# sensorHub.net
KiCad netlist of a schematic drawn in EAGLE
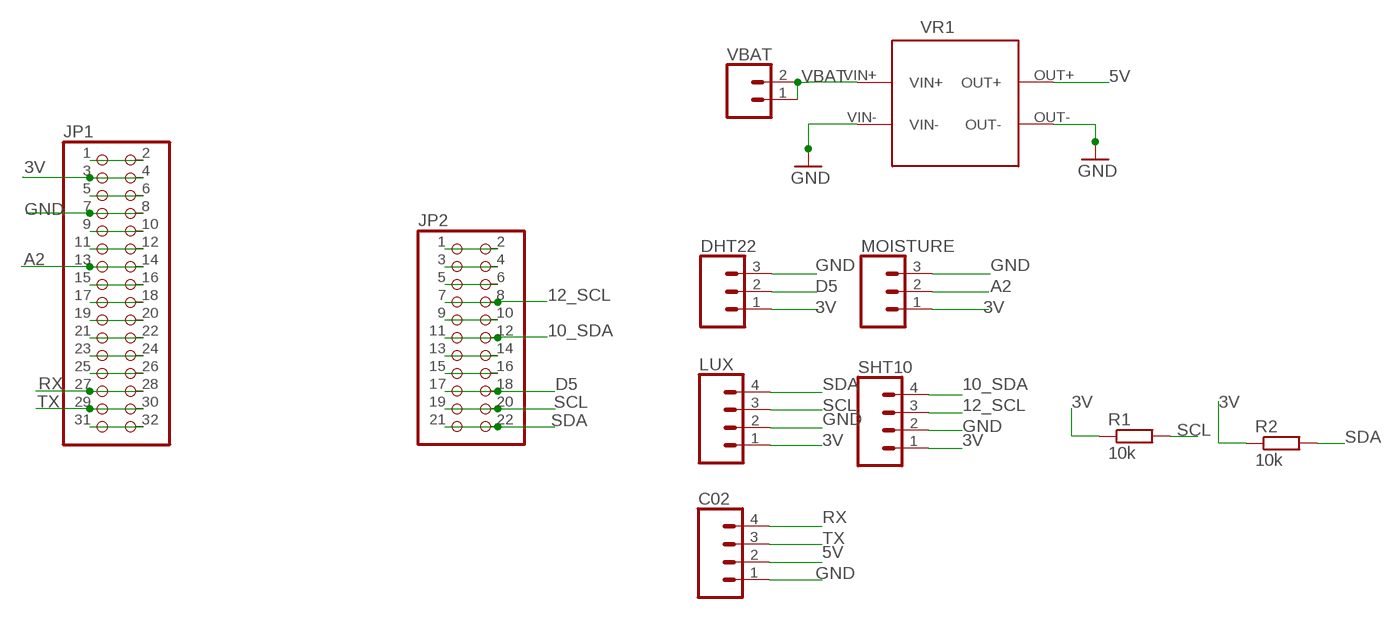
[diagram p0: schematic, sheet 1]

(export (version "E")
  (design (tool "Eeschema 10.0.6"))
  (components
    (comp (ref "C02")
      (value "CONN_04SCREW")
      (footprint "eagle-import:SCREWTERMINAL-3.5MM-4")
      (libsource (lib "eagle-import") (part "CONN_04SCREW"))
    )
    (comp (ref "DHT22")
      (value "CONN_03SCREW")
      (footprint "eagle-import:SCREWTERMINAL-3.5MM-3")
      (libsource (lib "eagle-import") (part "CONN_03SCREW"))
    )
    (comp (ref "JP1")
      (value "PINHD-2X16")
      (footprint "eagle-import:2X16")
      (libsource (lib "eagle-import") (part "PINHD-2X16"))
    )
    (comp (ref "JP2")
      (value "PINHD-2X11")
      (footprint "eagle-import:2X11")
      (libsource (lib "eagle-import") (part "PINHD-2X11"))
    )
    (comp (ref "LUX")
      (value "CONN_04SCREW")
      (footprint "eagle-import:SCREWTERMINAL-3.5MM-4")
      (libsource (lib "eagle-import") (part "CONN_04SCREW"))
    )
    (comp (ref "MOISTURE")
      (value "CONN_03SCREW")
      (footprint "eagle-import:SCREWTERMINAL-3.5MM-3")
      (libsource (lib "eagle-import") (part "CONN_03SCREW"))
    )
    (comp (ref "R1")
      (value "10k")
      (footprint "eagle-import:0207_10")
      (libsource (lib "eagle-import") (part "R-EU_0207/10"))
    )
    (comp (ref "R2")
      (value "10k")
      (footprint "eagle-import:0207_10")
      (libsource (lib "eagle-import") (part "R-EU_0207/10"))
    )
    (comp (ref "SHT10")
      (value "CONN_04SCREW")
      (footprint "eagle-import:SCREWTERMINAL-3.5MM-4")
      (libsource (lib "eagle-import") (part "CONN_04SCREW"))
    )
    (comp (ref "VBAT")
      (value "CONN_02")
      (footprint "eagle-import:1X02")
      (libsource (lib "eagle-import") (part "CONN_02"))
    )
    (comp (ref "VR1")
      (value "MT3608THROUGH_HOLE")
      (footprint "eagle-import:MT3608")
      (libsource (lib "eagle-import") (part "MT3608THROUGH_HOLE"))
    )
  )
  (nets
    (net (code "1") (name "/3V") (class "Default")
      (node (ref "DHT22") (pin "1") (pinfunction "1_1") (pintype "passive"))
      (node (ref "JP1") (pin "3") (pinfunction "3_3") (pintype "passive"))
      (node (ref "JP1") (pin "4") (pinfunction "4_4") (pintype "passive"))
      (node (ref "LUX") (pin "1") (pinfunction "1_1") (pintype "passive"))
      (node (ref "MOISTURE") (pin "1") (pinfunction "1_1") (pintype "passive"))
      (node (ref "R1") (pin "1") (pinfunction "1_1") (pintype "passive"))
      (node (ref "R2") (pin "1") (pinfunction "1_1") (pintype "passive"))
      (node (ref "SHT10") (pin "1") (pinfunction "1_1") (pintype "passive"))
    )
    (net (code "2") (name "/5V") (class "Default")
      (node (ref "C02") (pin "2") (pinfunction "2_2") (pintype "passive"))
      (node (ref "VR1") (pin "OUT+") (pinfunction "OUT+_OUT+") (pintype "power_in"))
    )
    (net (code "3") (name "/10_SDA") (class "Default")
      (node (ref "JP2") (pin "11") (pinfunction "11_11") (pintype "passive"))
      (node (ref "JP2") (pin "12") (pinfunction "12_12") (pintype "passive"))
      (node (ref "SHT10") (pin "4") (pinfunction "4_4") (pintype "passive"))
    )
    (net (code "4") (name "/12_SCL") (class "Default")
      (node (ref "JP2") (pin "7") (pinfunction "7_7") (pintype "passive"))
      (node (ref "JP2") (pin "8") (pinfunction "8_8") (pintype "passive"))
      (node (ref "SHT10") (pin "3") (pinfunction "3_3") (pintype "passive"))
    )
    (net (code "5") (name "/A2") (class "Default")
      (node (ref "JP1") (pin "13") (pinfunction "13_13") (pintype "passive"))
      (node (ref "JP1") (pin "14") (pinfunction "14_14") (pintype "passive"))
      (node (ref "MOISTURE") (pin "2") (pinfunction "2_2") (pintype "passive"))
    )
    (net (code "6") (name "/D5") (class "Default")
      (node (ref "DHT22") (pin "2") (pinfunction "2_2") (pintype "passive"))
      (node (ref "JP2") (pin "17") (pinfunction "17_17") (pintype "passive"))
      (node (ref "JP2") (pin "18") (pinfunction "18_18") (pintype "passive"))
    )
    (net (code "7") (name "/RX") (class "Default")
      (node (ref "C02") (pin "4") (pinfunction "4_4") (pintype "passive"))
      (node (ref "JP1") (pin "27") (pinfunction "27_27") (pintype "passive"))
      (node (ref "JP1") (pin "28") (pinfunction "28_28") (pintype "passive"))
    )
    (net (code "8") (name "/SCL") (class "Default")
      (node (ref "JP2") (pin "19") (pinfunction "19_19") (pintype "passive"))
      (node (ref "JP2") (pin "20") (pinfunction "20_20") (pintype "passive"))
      (node (ref "LUX") (pin "3") (pinfunction "3_3") (pintype "passive"))
      (node (ref "R1") (pin "2") (pinfunction "2_2") (pintype "passive"))
    )
    (net (code "9") (name "/SDA") (class "Default")
      (node (ref "JP2") (pin "21") (pinfunction "21_21") (pintype "passive"))
      (node (ref "JP2") (pin "22") (pinfunction "22_22") (pintype "passive"))
      (node (ref "LUX") (pin "4") (pinfunction "4_4") (pintype "passive"))
      (node (ref "R2") (pin "2") (pinfunction "2_2") (pintype "passive"))
    )
    (net (code "10") (name "/TX") (class "Default")
      (node (ref "C02") (pin "3") (pinfunction "3_3") (pintype "passive"))
      (node (ref "JP1") (pin "29") (pinfunction "29_29") (pintype "passive"))
      (node (ref "JP1") (pin "30") (pinfunction "30_30") (pintype "passive"))
    )
    (net (code "11") (name "/VBAT") (class "Default")
      (node (ref "VBAT") (pin "1") (pinfunction "1_1") (pintype "passive"))
      (node (ref "VBAT") (pin "2") (pinfunction "2_2") (pintype "passive"))
      (node (ref "VR1") (pin "VIN+") (pinfunction "VIN+_VIN+") (pintype "power_in"))
    )
    (net (code "12") (name "GND") (class "Default")
      (node (ref "C02") (pin "1") (pinfunction "1_1") (pintype "passive"))
      (node (ref "DHT22") (pin "3") (pinfunction "3_3") (pintype "passive"))
      (node (ref "JP1") (pin "7") (pinfunction "7_7") (pintype "passive"))
      (node (ref "JP1") (pin "8") (pinfunction "8_8") (pintype "passive"))
      (node (ref "LUX") (pin "2") (pinfunction "2_2") (pintype "passive"))
      (node (ref "MOISTURE") (pin "3") (pinfunction "3_3") (pintype "passive"))
      (node (ref "SHT10") (pin "2") (pinfunction "2_2") (pintype "passive"))
      (node (ref "VR1") (pin "OUT-") (pinfunction "OUT-_OUT-") (pintype "power_in"))
      (node (ref "VR1") (pin "VIN-") (pinfunction "VIN-_VIN-") (pintype "power_in"))
    )
    (net (code "13") (name "Net-(JP1-Pad1)") (class "Default")
      (node (ref "JP1") (pin "1") (pinfunction "1_1") (pintype "passive"))
      (node (ref "JP1") (pin "2") (pinfunction "2_2") (pintype "passive"))
    )
    (net (code "14") (name "Net-(JP1-Pad5)") (class "Default")
      (node (ref "JP1") (pin "5") (pinfunction "5_5") (pintype "passive"))
      (node (ref "JP1") (pin "6") (pinfunction "6_6") (pintype "passive"))
    )
    (net (code "15") (name "Net-(JP1-Pad10)") (class "Default")
      (node (ref "JP1") (pin "10") (pinfunction "10_10") (pintype "passive"))
      (node (ref "JP1") (pin "9") (pinfunction "9_9") (pintype "passive"))
    )
    (net (code "16") (name "Net-(JP1-Pad11)") (class "Default")
      (node (ref "JP1") (pin "11") (pinfunction "11_11") (pintype "passive"))
      (node (ref "JP1") (pin "12") (pinfunction "12_12") (pintype "passive"))
    )
    (net (code "17") (name "Net-(JP1-Pad15)") (class "Default")
      (node (ref "JP1") (pin "15") (pinfunction "15_15") (pintype "passive"))
      (node (ref "JP1") (pin "16") (pinfunction "16_16") (pintype "passive"))
    )
    (net (code "18") (name "Net-(JP1-Pad17)") (class "Default")
      (node (ref "JP1") (pin "17") (pinfunction "17_17") (pintype "passive"))
      (node (ref "JP1") (pin "18") (pinfunction "18_18") (pintype "passive"))
    )
    (net (code "19") (name "Net-(JP1-Pad19)") (class "Default")
      (node (ref "JP1") (pin "19") (pinfunction "19_19") (pintype "passive"))
      (node (ref "JP1") (pin "20") (pinfunction "20_20") (pintype "passive"))
    )
    (net (code "20") (name "Net-(JP1-Pad21)") (class "Default")
      (node (ref "JP1") (pin "21") (pinfunction "21_21") (pintype "passive"))
      (node (ref "JP1") (pin "22") (pinfunction "22_22") (pintype "passive"))
    )
    (net (code "21") (name "Net-(JP1-Pad23)") (class "Default")
      (node (ref "JP1") (pin "23") (pinfunction "23_23") (pintype "passive"))
      (node (ref "JP1") (pin "24") (pinfunction "24_24") (pintype "passive"))
    )
    (net (code "22") (name "Net-(JP1-Pad25)") (class "Default")
      (node (ref "JP1") (pin "25") (pinfunction "25_25") (pintype "passive"))
      (node (ref "JP1") (pin "26") (pinfunction "26_26") (pintype "passive"))
    )
    (net (code "23") (name "Net-(JP1-Pad31)") (class "Default")
      (node (ref "JP1") (pin "31") (pinfunction "31_31") (pintype "passive"))
      (node (ref "JP1") (pin "32") (pinfunction "32_32") (pintype "passive"))
    )
    (net (code "24") (name "Net-(JP2-Pad1)") (class "Default")
      (node (ref "JP2") (pin "1") (pinfunction "1_1") (pintype "passive"))
      (node (ref "JP2") (pin "2") (pinfunction "2_2") (pintype "passive"))
    )
    (net (code "25") (name "Net-(JP2-Pad3)") (class "Default")
      (node (ref "JP2") (pin "3") (pinfunction "3_3") (pintype "passive"))
      (node (ref "JP2") (pin "4") (pinfunction "4_4") (pintype "passive"))
    )
    (net (code "26") (name "Net-(JP2-Pad5)") (class "Default")
      (node (ref "JP2") (pin "5") (pinfunction "5_5") (pintype "passive"))
      (node (ref "JP2") (pin "6") (pinfunction "6_6") (pintype "passive"))
    )
    (net (code "27") (name "Net-(JP2-Pad10)") (class "Default")
      (node (ref "JP2") (pin "10") (pinfunction "10_10") (pintype "passive"))
      (node (ref "JP2") (pin "9") (pinfunction "9_9") (pintype "passive"))
    )
    (net (code "28") (name "Net-(JP2-Pad13)") (class "Default")
      (node (ref "JP2") (pin "13") (pinfunction "13_13") (pintype "passive"))
      (node (ref "JP2") (pin "14") (pinfunction "14_14") (pintype "passive"))
    )
    (net (code "29") (name "Net-(JP2-Pad15)") (class "Default")
      (node (ref "JP2") (pin "15") (pinfunction "15_15") (pintype "passive"))
      (node (ref "JP2") (pin "16") (pinfunction "16_16") (pintype "passive"))
    )
  )
)
